# TSOC_USBUART2.net
KiCad netlist of a schematic drawn in EAGLE
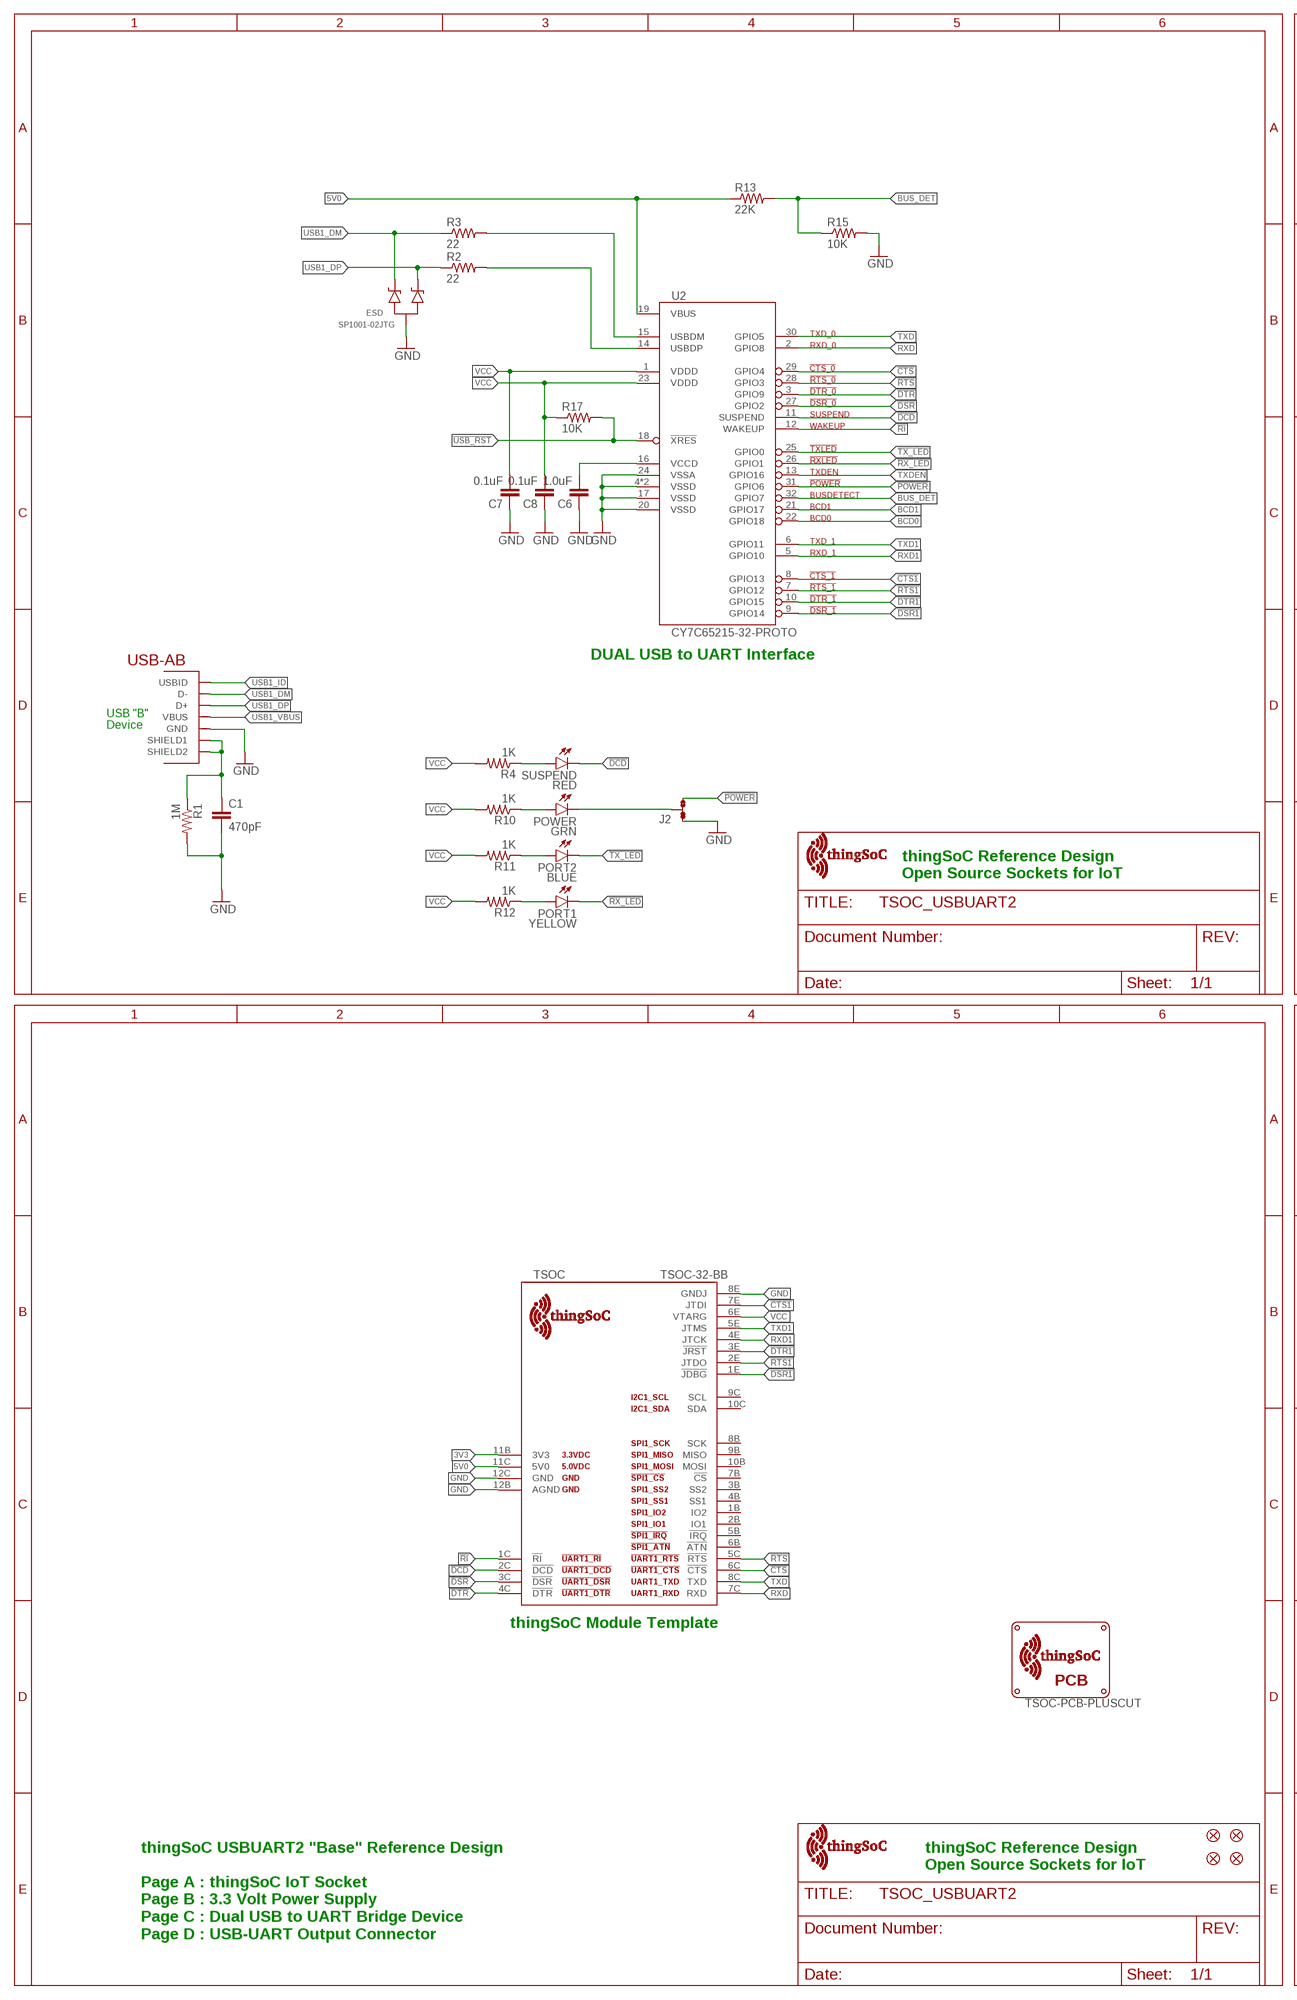
[diagram p0: schematic, sheet 1, part 1 of 2]
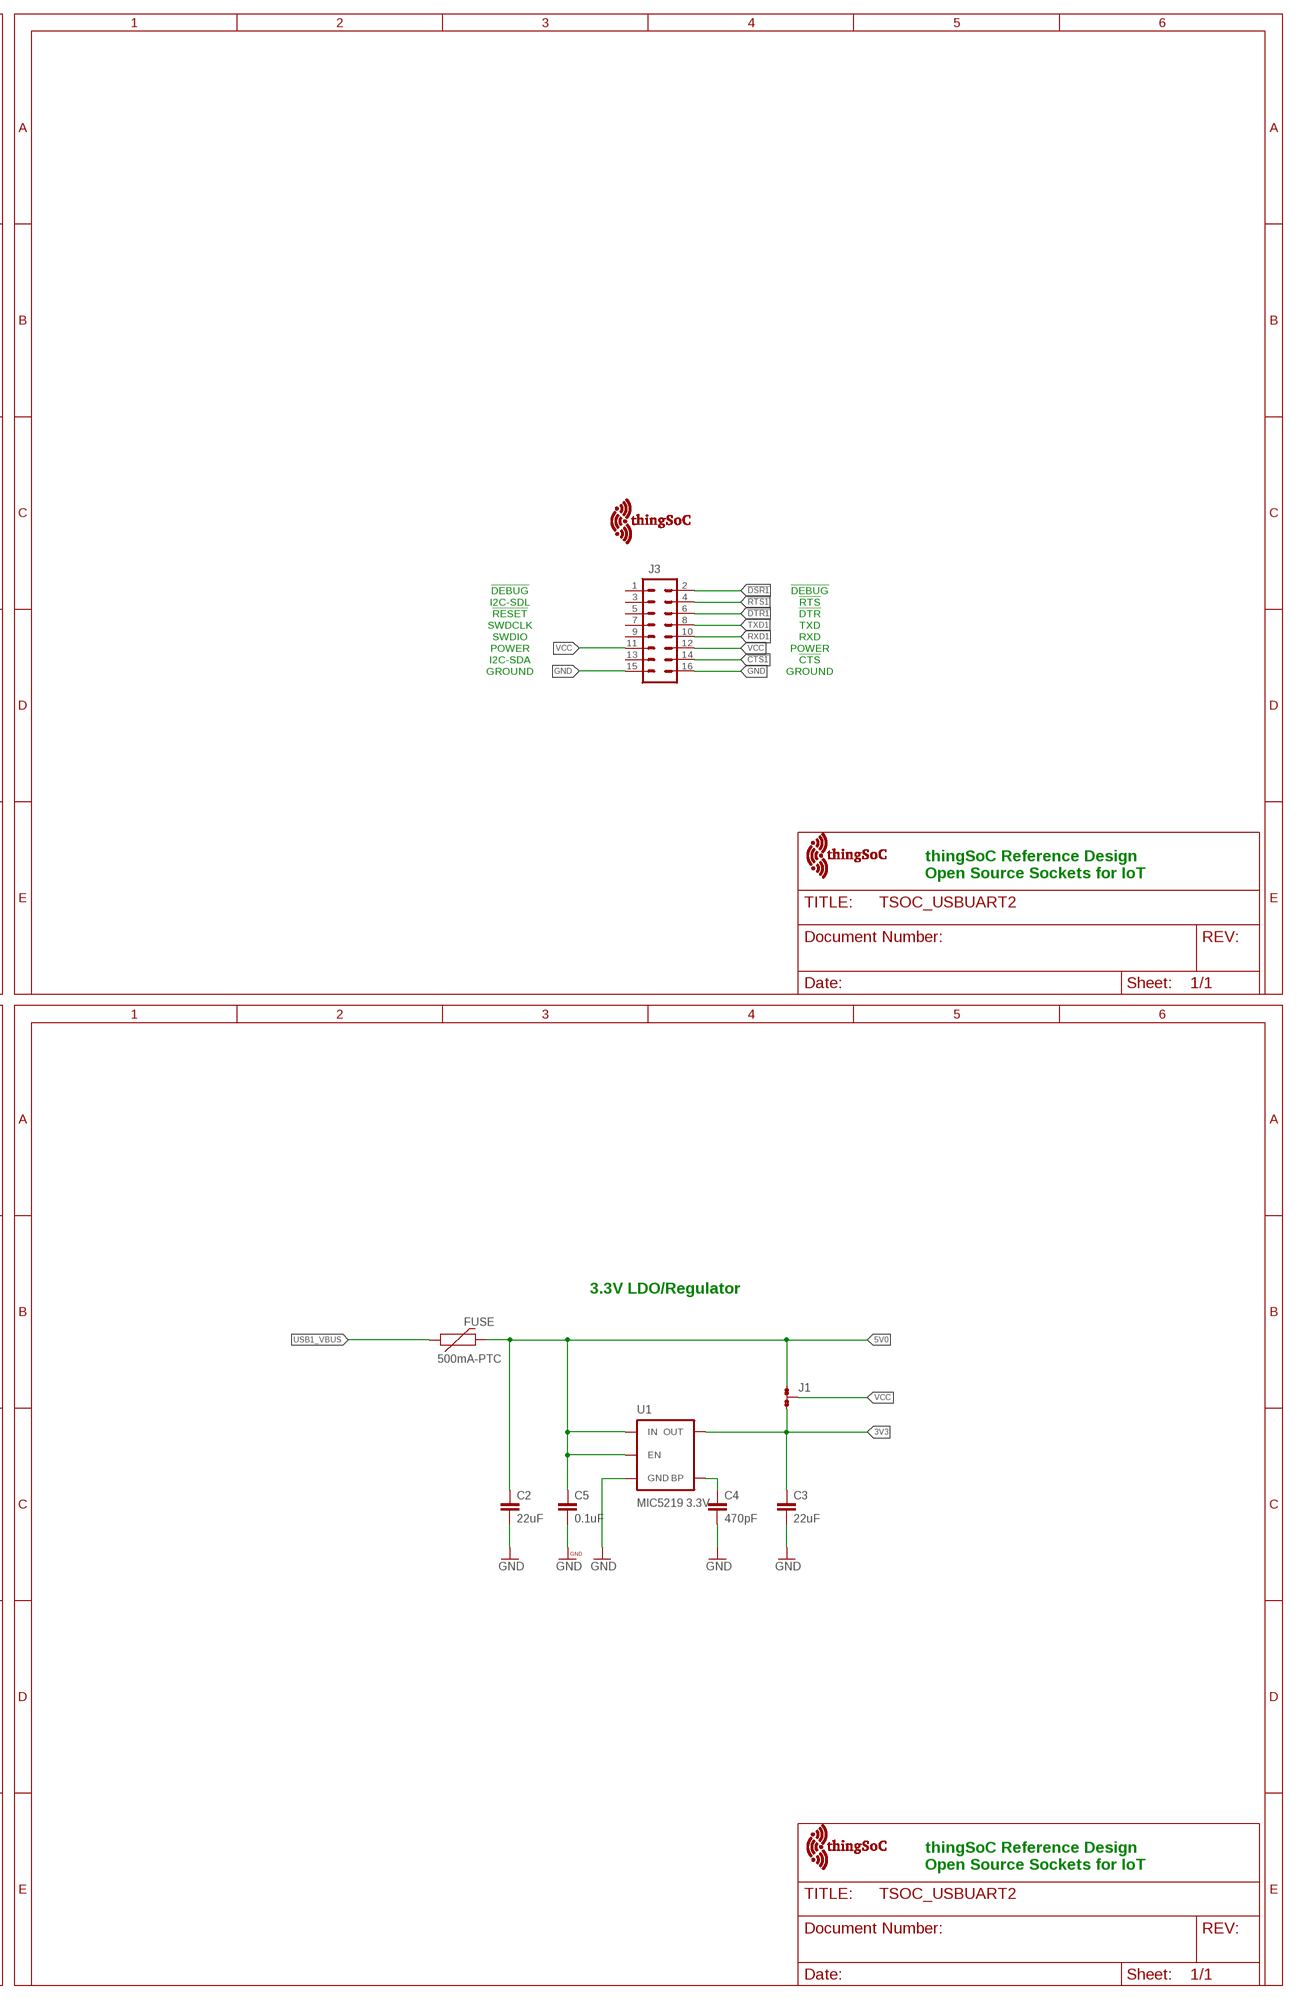
[diagram p1: schematic, sheet 1, part 2 of 2]

(export (version "E")
  (design (tool "Eeschema 10.0.6"))
  (components
    (comp (ref "C1")
      (value "470pF")
      (footprint "eagle-import:EIA-0603")
      (libsource (lib "eagle-import") (part "CAP-0603"))
    )
    (comp (ref "C2")
      (value "22uF")
      (footprint "eagle-import:EIA-1206")
      (libsource (lib "eagle-import") (part "CAP-1206"))
    )
    (comp (ref "C3")
      (value "22uF")
      (footprint "eagle-import:EIA-1206")
      (libsource (lib "eagle-import") (part "CAP-1206"))
    )
    (comp (ref "C4")
      (value "470pF")
      (footprint "eagle-import:EIA-0603")
      (libsource (lib "eagle-import") (part "CAP-0603"))
    )
    (comp (ref "C5")
      (value "0.1uF")
      (footprint "eagle-import:EIA-0603")
      (libsource (lib "eagle-import") (part "CAP-0603"))
    )
    (comp (ref "C6")
      (value "1.0uF")
      (footprint "eagle-import:EIA-0603")
      (libsource (lib "eagle-import") (part "CAP-0603"))
    )
    (comp (ref "C7")
      (value "0.1uF")
      (footprint "eagle-import:EIA-0603")
      (libsource (lib "eagle-import") (part "CAP-0603"))
    )
    (comp (ref "C8")
      (value "0.1uF")
      (footprint "eagle-import:EIA-0603")
      (libsource (lib "eagle-import") (part "CAP-0603"))
    )
    (comp (ref "ESD")
      (value "SP1001-02JTG")
      (footprint "eagle-import:SC70-3")
      (libsource (lib "eagle-import") (part "SP1001-02JTG"))
    )
    (comp (ref "FID1")
      (value "FIDUCIALUFIDUCIAL")
      (footprint "eagle-import:MICRO-FIDUCIAL")
      (libsource (lib "eagle-import") (part "FIDUCIALUFIDUCIAL"))
    )
    (comp (ref "FID2")
      (value "FIDUCIALUFIDUCIAL")
      (footprint "eagle-import:MICRO-FIDUCIAL")
      (libsource (lib "eagle-import") (part "FIDUCIALUFIDUCIAL"))
    )
    (comp (ref "FID3")
      (value "FIDUCIALUFIDUCIAL")
      (footprint "eagle-import:MICRO-FIDUCIAL")
      (libsource (lib "eagle-import") (part "FIDUCIALUFIDUCIAL"))
    )
    (comp (ref "FID4")
      (value "FIDUCIALUFIDUCIAL")
      (footprint "eagle-import:MICRO-FIDUCIAL")
      (libsource (lib "eagle-import") (part "FIDUCIALUFIDUCIAL"))
    )
    (comp (ref "FUSE")
      (value "500mA-PTC")
      (footprint "eagle-import:PTC-1206")
      (libsource (lib "eagle-import") (part "PTCSMD"))
    )
    (comp (ref "J1")
      (value "JMP-3-1_2")
      (footprint "eagle-import:JMP-3-1_2")
      (libsource (lib "eagle-import") (part "JMP-3-1_2"))
    )
    (comp (ref "J2")
      (value "JMP-3-1_2")
      (footprint "eagle-import:JMP-3-1_2")
      (libsource (lib "eagle-import") (part "JMP-3-1_2"))
    )
    (comp (ref "J3")
      (value "M08X2")
      (footprint "eagle-import:2X8")
      (libsource (lib "eagle-import") (part "M08X2"))
    )
    (comp (ref "PORT1")
      (value "YELLOW")
      (footprint "eagle-import:LED-0603")
      (libsource (lib "eagle-import") (part "LED0603"))
    )
    (comp (ref "PORT2")
      (value "BLUE")
      (footprint "eagle-import:LED-0603")
      (libsource (lib "eagle-import") (part "LED0603"))
    )
    (comp (ref "POWER")
      (value "GRN")
      (footprint "eagle-import:LED-0603")
      (libsource (lib "eagle-import") (part "LED0603"))
    )
    (comp (ref "R1")
      (value "1M")
      (footprint "eagle-import:EIA-0603")
      (libsource (lib "eagle-import") (part "RESISTOR-0603"))
    )
    (comp (ref "R2")
      (value "22")
      (footprint "eagle-import:EIA-0603")
      (libsource (lib "eagle-import") (part "RESISTOR-0603"))
    )
    (comp (ref "R3")
      (value "22")
      (footprint "eagle-import:EIA-0603")
      (libsource (lib "eagle-import") (part "RESISTOR-0603"))
    )
    (comp (ref "R4")
      (value "1K")
      (footprint "eagle-import:EIA-0603")
      (libsource (lib "eagle-import") (part "RESISTOR-0603"))
    )
    (comp (ref "R10")
      (value "1K")
      (footprint "eagle-import:EIA-0603")
      (libsource (lib "eagle-import") (part "RESISTOR-0603"))
    )
    (comp (ref "R11")
      (value "1K")
      (footprint "eagle-import:EIA-0603")
      (libsource (lib "eagle-import") (part "RESISTOR-0603"))
    )
    (comp (ref "R12")
      (value "1K")
      (footprint "eagle-import:EIA-0603")
      (libsource (lib "eagle-import") (part "RESISTOR-0603"))
    )
    (comp (ref "R13")
      (value "22K")
      (footprint "eagle-import:EIA-0603")
      (libsource (lib "eagle-import") (part "RESISTOR-0603"))
    )
    (comp (ref "R15")
      (value "10K")
      (footprint "eagle-import:EIA-0603")
      (libsource (lib "eagle-import") (part "RESISTOR-0603"))
    )
    (comp (ref "R17")
      (value "10K")
      (footprint "eagle-import:EIA-0603")
      (libsource (lib "eagle-import") (part "RESISTOR-0603"))
    )
    (comp (ref "SUSPEND")
      (value "RED")
      (footprint "eagle-import:LED-0603")
      (libsource (lib "eagle-import") (part "LED0603"))
    )
    (comp (ref "TSOC")
      (value "TSOC-32-BB")
      (footprint "eagle-import:TSOC-BB-S32")
      (libsource (lib "eagle-import") (part "TSOC-32-BB"))
    )
    (comp (ref "U$3")
      (value "TSOC-LOGO-LRG")
      (footprint "eagle-import:TSOC-LOGO-LRG")
      (libsource (lib "eagle-import") (part "TSOC-LOGO-LRG"))
    )
    (comp (ref "U$4")
      (value "TSOC-LOGO")
      (footprint "eagle-import:TSOC-LOGO-BLANK")
      (libsource (lib "eagle-import") (part "TSOC-LOGO"))
    )
    (comp (ref "U$5")
      (value "TSOC-LOGO")
      (footprint "eagle-import:TSOC-LOGO-BLANK")
      (libsource (lib "eagle-import") (part "TSOC-LOGO"))
    )
    (comp (ref "U$6")
      (value "TSOC-LOGO")
      (footprint "eagle-import:TSOC-LOGO-BLANK")
      (libsource (lib "eagle-import") (part "TSOC-LOGO"))
    )
    (comp (ref "U$7")
      (value "TSOC-PCB-PLUSCUT")
      (footprint "eagle-import:TSOC-BB-BRD-PLUS-CUT")
      (libsource (lib "eagle-import") (part "TSOC-PCB-PLUSCUT"))
    )
    (comp (ref "U$8")
      (value "TSOC-LOGO-SMALL")
      (footprint "eagle-import:TSOC-LOGO-SML")
      (libsource (lib "eagle-import") (part "TSOC-LOGO-SMALL"))
    )
    (comp (ref "U1")
      (value "MIC5219 3.3V")
      (footprint "eagle-import:SOT23-5")
      (libsource (lib "eagle-import") (part "V_REG_MIC52193.3V"))
    )
    (comp (ref "U2")
      (value "CY7C65215-32-PROTO")
      (footprint "eagle-import:QFN32-PROTO")
      (libsource (lib "eagle-import") (part "CY7C65215-32-PROTO"))
    )
    (comp (ref "USB")
      (value "USB_AB")
      (footprint "eagle-import:USB-AB-MICRO-SMD")
      (libsource (lib "eagle-import") (part "USB_AB"))
    )
  )
  (nets
    (net (code "1") (name "/~{CTS1}") (class "Default")
      (node (ref "J3") (pin "14") (pinfunction "14_14") (pintype "passive"))
      (node (ref "TSOC") (pin "7E") (pinfunction "JTDI_7E") (pintype "bidirectional"))
      (node (ref "U2") (pin "8") (pinfunction "GPIO13_8") (pintype "input"))
    )
    (net (code "2") (name "/~{CTS}") (class "Default")
      (node (ref "TSOC") (pin "6C") (pinfunction "~{CTS}_6C") (pintype "bidirectional"))
      (node (ref "U2") (pin "29") (pinfunction "GPIO4_29") (pintype "input"))
    )
    (net (code "3") (name "/~{DCD}") (class "Default")
      (node (ref "SUSPEND") (pin "C") (pinfunction "C_C") (pintype "passive"))
      (node (ref "TSOC") (pin "2C") (pinfunction "~{DCD}_2C") (pintype "bidirectional"))
      (node (ref "U2") (pin "11") (pinfunction "SUSPEND_11") (pintype "input"))
    )
    (net (code "4") (name "/~{DSR1}") (class "Default")
      (node (ref "J3") (pin "2") (pinfunction "2_2") (pintype "passive"))
      (node (ref "TSOC") (pin "1E") (pinfunction "~{JDBG}_1E") (pintype "bidirectional"))
      (node (ref "U2") (pin "9") (pinfunction "GPIO14_9") (pintype "input"))
    )
    (net (code "5") (name "/~{DSR}") (class "Default")
      (node (ref "TSOC") (pin "3C") (pinfunction "~{DSR}_3C") (pintype "bidirectional"))
      (node (ref "U2") (pin "27") (pinfunction "GPIO2_27") (pintype "input"))
    )
    (net (code "6") (name "/~{DTR1}") (class "Default")
      (node (ref "J3") (pin "6") (pinfunction "6_6") (pintype "passive"))
      (node (ref "TSOC") (pin "3E") (pinfunction "~{JRST}_3E") (pintype "bidirectional"))
      (node (ref "U2") (pin "10") (pinfunction "GPIO15_10") (pintype "output"))
    )
    (net (code "7") (name "/~{DTR}") (class "Default")
      (node (ref "TSOC") (pin "4C") (pinfunction "~{DTR}_4C") (pintype "bidirectional"))
      (node (ref "U2") (pin "3") (pinfunction "GPIO9_3") (pintype "output"))
    )
    (net (code "8") (name "/~{POWER}") (class "Default")
      (node (ref "J2") (pin "3") (pinfunction "3_3") (pintype "passive"))
      (node (ref "U2") (pin "31") (pinfunction "GPIO6_31") (pintype "input"))
    )
    (net (code "9") (name "/~{RI}") (class "Default")
      (node (ref "TSOC") (pin "1C") (pinfunction "~{RI}_1C") (pintype "bidirectional"))
      (node (ref "U2") (pin "12") (pinfunction "WAKEUP_12") (pintype "input"))
    )
    (net (code "10") (name "/~{RTS1}") (class "Default")
      (node (ref "J3") (pin "4") (pinfunction "4_4") (pintype "passive"))
      (node (ref "TSOC") (pin "2E") (pinfunction "JTDO_2E") (pintype "bidirectional"))
      (node (ref "U2") (pin "7") (pinfunction "GPIO12_7") (pintype "output"))
    )
    (net (code "11") (name "/~{RTS}") (class "Default")
      (node (ref "TSOC") (pin "5C") (pinfunction "~{RTS}_5C") (pintype "bidirectional"))
      (node (ref "U2") (pin "28") (pinfunction "GPIO3_28") (pintype "output"))
    )
    (net (code "12") (name "/~{RX_LED}") (class "Default")
      (node (ref "PORT1") (pin "C") (pinfunction "C_C") (pintype "passive"))
      (node (ref "U2") (pin "26") (pinfunction "GPIO1_26") (pintype "input"))
    )
    (net (code "13") (name "/~{TX_LED}") (class "Default")
      (node (ref "PORT2") (pin "C") (pinfunction "C_C") (pintype "passive"))
      (node (ref "U2") (pin "25") (pinfunction "GPIO0_25") (pintype "input"))
    )
    (net (code "14") (name "/~{USB_RST}") (class "Default")
      (node (ref "R17") (pin "2") (pinfunction "2_2") (pintype "passive"))
      (node (ref "U2") (pin "18") (pinfunction "~{XRES}_18") (pintype "input"))
    )
    (net (code "15") (name "3V3") (class "Default")
      (node (ref "C3") (pin "1") (pinfunction "1_1") (pintype "passive"))
      (node (ref "J1") (pin "3") (pinfunction "3_3") (pintype "passive"))
      (node (ref "TSOC") (pin "11B") (pinfunction "3V3_11B") (pintype "bidirectional"))
      (node (ref "U1") (pin "5") (pinfunction "OUT_5") (pintype "passive"))
    )
    (net (code "16") (name "5V0") (class "Default")
      (node (ref "C2") (pin "1") (pinfunction "1_1") (pintype "passive"))
      (node (ref "C5") (pin "1") (pinfunction "1_1") (pintype "passive"))
      (node (ref "FUSE") (pin "2") (pinfunction "2_2") (pintype "bidirectional"))
      (node (ref "J1") (pin "1") (pinfunction "1_1") (pintype "passive"))
      (node (ref "R13") (pin "1") (pinfunction "1_1") (pintype "passive"))
      (node (ref "TSOC") (pin "11C") (pinfunction "5V0_11C") (pintype "bidirectional"))
      (node (ref "U1") (pin "1") (pinfunction "IN_1") (pintype "input"))
      (node (ref "U1") (pin "3") (pinfunction "EN_3") (pintype "input"))
      (node (ref "U2") (pin "19") (pinfunction "VBUS_19") (pintype "power_in"))
    )
    (net (code "17") (name "BCD0") (class "Default")
      (node (ref "U2") (pin "22") (pinfunction "GPIO18_22") (pintype "input"))
    )
    (net (code "18") (name "BCD1") (class "Default")
      (node (ref "U2") (pin "21") (pinfunction "GPIO17_21") (pintype "input"))
    )
    (net (code "19") (name "BUS_DET") (class "Default")
      (node (ref "R13") (pin "2") (pinfunction "2_2") (pintype "passive"))
      (node (ref "R15") (pin "1") (pinfunction "1_1") (pintype "passive"))
      (node (ref "U2") (pin "32") (pinfunction "GPIO7_32") (pintype "input"))
    )
    (net (code "20") (name "GND") (class "Default")
      (node (ref "C1") (pin "2") (pinfunction "2_2") (pintype "passive"))
      (node (ref "C2") (pin "2") (pinfunction "2_2") (pintype "passive"))
      (node (ref "C3") (pin "2") (pinfunction "2_2") (pintype "passive"))
      (node (ref "C4") (pin "2") (pinfunction "2_2") (pintype "passive"))
      (node (ref "C5") (pin "2") (pinfunction "2_2") (pintype "passive"))
      (node (ref "C6") (pin "1") (pinfunction "1_1") (pintype "passive"))
      (node (ref "C7") (pin "1") (pinfunction "1_1") (pintype "passive"))
      (node (ref "C8") (pin "1") (pinfunction "1_1") (pintype "passive"))
      (node (ref "ESD") (pin "3") (pinfunction "A_3") (pintype "passive"))
      (node (ref "J2") (pin "1") (pinfunction "1_1") (pintype "passive"))
      (node (ref "J3") (pin "15") (pinfunction "15_15") (pintype "passive"))
      (node (ref "J3") (pin "16") (pinfunction "16_16") (pintype "passive"))
      (node (ref "R1") (pin "2") (pinfunction "2_2") (pintype "passive"))
      (node (ref "R15") (pin "2") (pinfunction "2_2") (pintype "passive"))
      (node (ref "TSOC") (pin "12B") (pinfunction "AGND_12B") (pintype "bidirectional"))
      (node (ref "TSOC") (pin "12C") (pinfunction "GND_12C") (pintype "bidirectional"))
      (node (ref "TSOC") (pin "8E") (pinfunction "GNDJ_8E") (pintype "bidirectional"))
      (node (ref "U1") (pin "2") (pinfunction "GND_2") (pintype "input"))
      (node (ref "U2") (pin "17") (pinfunction "VSSD_17") (pintype "power_in"))
      (node (ref "U2") (pin "20") (pinfunction "VSSD_20") (pintype "power_in"))
      (node (ref "U2") (pin "24") (pinfunction "VSSA_24") (pintype "power_in"))
      (node (ref "U2") (pin "4") (pinfunction "VSSD_4") (pintype "power_in"))
      (node (ref "U2") (pin "EXP") (pinfunction "VSSD_EXP") (pintype "power_in"))
      (node (ref "USB") (pin "GND") (pinfunction "GND_GND") (pintype "bidirectional"))
    )
    (net (code "21") (name "Net-(C1-Pad1)") (class "Default")
      (node (ref "C1") (pin "1") (pinfunction "1_1") (pintype "passive"))
      (node (ref "R1") (pin "1") (pinfunction "1_1") (pintype "passive"))
      (node (ref "USB") (pin "SHIELD1") (pinfunction "SHIELD1_SHIELD1") (pintype "bidirectional"))
      (node (ref "USB") (pin "SHIELD2") (pinfunction "SHIELD2_SHIELD2") (pintype "bidirectional"))
    )
    (net (code "22") (name "Net-(J2-Pad2)") (class "Default")
      (node (ref "J2") (pin "2") (pinfunction "2_2") (pintype "passive"))
      (node (ref "POWER") (pin "C") (pinfunction "C_C") (pintype "passive"))
    )
    (net (code "23") (name "Net-(PORT1-PadA)") (class "Default")
      (node (ref "PORT1") (pin "A") (pinfunction "A_A") (pintype "passive"))
      (node (ref "R12") (pin "1") (pinfunction "1_1") (pintype "passive"))
    )
    (net (code "24") (name "Net-(PORT2-PadA)") (class "Default")
      (node (ref "PORT2") (pin "A") (pinfunction "A_A") (pintype "passive"))
      (node (ref "R11") (pin "1") (pinfunction "1_1") (pintype "passive"))
    )
    (net (code "25") (name "Net-(POWER-PadA)") (class "Default")
      (node (ref "POWER") (pin "A") (pinfunction "A_A") (pintype "passive"))
      (node (ref "R10") (pin "1") (pinfunction "1_1") (pintype "passive"))
    )
    (net (code "26") (name "Net-(R4-Pad1)") (class "Default")
      (node (ref "R4") (pin "1") (pinfunction "1_1") (pintype "passive"))
      (node (ref "SUSPEND") (pin "A") (pinfunction "A_A") (pintype "passive"))
    )
    (net (code "27") (name "Net-(U1-BP)") (class "Default")
      (node (ref "C4") (pin "1") (pinfunction "1_1") (pintype "passive"))
      (node (ref "U1") (pin "4") (pinfunction "BP_4") (pintype "input"))
    )
    (net (code "28") (name "Net-(U2-USBDM)") (class "Default")
      (node (ref "R3") (pin "2") (pinfunction "2_2") (pintype "passive"))
      (node (ref "U2") (pin "15") (pinfunction "USBDM_15") (pintype "bidirectional"))
    )
    (net (code "29") (name "Net-(U2-USBDP)") (class "Default")
      (node (ref "R2") (pin "2") (pinfunction "2_2") (pintype "passive"))
      (node (ref "U2") (pin "14") (pinfunction "USBDP_14") (pintype "bidirectional"))
    )
    (net (code "30") (name "Net-(U2-VCCD)") (class "Default")
      (node (ref "C6") (pin "2") (pinfunction "2_2") (pintype "passive"))
      (node (ref "U2") (pin "16") (pinfunction "VCCD_16") (pintype "output"))
    )
    (net (code "31") (name "RXD") (class "Default")
      (node (ref "TSOC") (pin "7C") (pinfunction "RXD_7C") (pintype "bidirectional"))
      (node (ref "U2") (pin "2") (pinfunction "GPIO8_2") (pintype "input"))
    )
    (net (code "32") (name "RXD1") (class "Default")
      (node (ref "J3") (pin "10") (pinfunction "10_10") (pintype "passive"))
      (node (ref "TSOC") (pin "4E") (pinfunction "JTCK_4E") (pintype "bidirectional"))
      (node (ref "U2") (pin "5") (pinfunction "GPIO10_5") (pintype "input"))
    )
    (net (code "33") (name "TXD") (class "Default")
      (node (ref "TSOC") (pin "8C") (pinfunction "TXD_8C") (pintype "bidirectional"))
      (node (ref "U2") (pin "30") (pinfunction "GPIO5_30") (pintype "output"))
    )
    (net (code "34") (name "TXD1") (class "Default")
      (node (ref "J3") (pin "8") (pinfunction "8_8") (pintype "passive"))
      (node (ref "TSOC") (pin "5E") (pinfunction "JTMS_5E") (pintype "bidirectional"))
      (node (ref "U2") (pin "6") (pinfunction "GPIO11_6") (pintype "output"))
    )
    (net (code "35") (name "TXDEN") (class "Default")
      (node (ref "U2") (pin "13") (pinfunction "GPIO16_13") (pintype "output"))
    )
    (net (code "36") (name "USB1_DM") (class "Default")
      (node (ref "ESD") (pin "2") (pinfunction "C2_2") (pintype "passive"))
      (node (ref "R3") (pin "1") (pinfunction "1_1") (pintype "passive"))
      (node (ref "USB") (pin "D-") (pinfunction "D-_D-") (pintype "bidirectional"))
    )
    (net (code "37") (name "USB1_DP") (class "Default")
      (node (ref "ESD") (pin "1") (pinfunction "C1_1") (pintype "passive"))
      (node (ref "R2") (pin "1") (pinfunction "1_1") (pintype "passive"))
      (node (ref "USB") (pin "D+") (pinfunction "D+_D+") (pintype "bidirectional"))
    )
    (net (code "38") (name "USB1_ID") (class "Default")
      (node (ref "USB") (pin "ID") (pinfunction "USBID_ID") (pintype "bidirectional"))
    )
    (net (code "39") (name "USB1_VBUS") (class "Default")
      (node (ref "FUSE") (pin "1") (pinfunction "1_1") (pintype "bidirectional"))
      (node (ref "USB") (pin "VBUS") (pinfunction "VBUS_VBUS") (pintype "bidirectional"))
    )
    (net (code "40") (name "VCC") (class "Default")
      (node (ref "C7") (pin "2") (pinfunction "2_2") (pintype "passive"))
      (node (ref "C8") (pin "2") (pinfunction "2_2") (pintype "passive"))
      (node (ref "J1") (pin "2") (pinfunction "2_2") (pintype "passive"))
      (node (ref "J3") (pin "11") (pinfunction "11_11") (pintype "passive"))
      (node (ref "J3") (pin "12") (pinfunction "12_12") (pintype "passive"))
      (node (ref "R10") (pin "2") (pinfunction "2_2") (pintype "passive"))
      (node (ref "R11") (pin "2") (pinfunction "2_2") (pintype "passive"))
      (node (ref "R12") (pin "2") (pinfunction "2_2") (pintype "passive"))
      (node (ref "R17") (pin "1") (pinfunction "1_1") (pintype "passive"))
      (node (ref "R4") (pin "2") (pinfunction "2_2") (pintype "passive"))
      (node (ref "TSOC") (pin "6E") (pinfunction "VTARG_6E") (pintype "bidirectional"))
      (node (ref "U2") (pin "1") (pinfunction "VDDD_1") (pintype "power_in"))
      (node (ref "U2") (pin "23") (pinfunction "VDDD_23") (pintype "power_in"))
    )
    (net (code "41") (name "unconnected-(J3-Pad1)") (class "Default")
      (node (ref "J3") (pin "1") (pinfunction "1_1") (pintype "passive"))
    )
    (net (code "42") (name "unconnected-(J3-Pad3)") (class "Default")
      (node (ref "J3") (pin "3") (pinfunction "3_3") (pintype "passive"))
    )
    (net (code "43") (name "unconnected-(J3-Pad5)") (class "Default")
      (node (ref "J3") (pin "5") (pinfunction "5_5") (pintype "passive"))
    )
    (net (code "44") (name "unconnected-(J3-Pad7)") (class "Default")
      (node (ref "J3") (pin "7") (pinfunction "7_7") (pintype "passive"))
    )
    (net (code "45") (name "unconnected-(J3-Pad9)") (class "Default")
      (node (ref "J3") (pin "9") (pinfunction "9_9") (pintype "passive"))
    )
    (net (code "46") (name "unconnected-(J3-Pad13)") (class "Default")
      (node (ref "J3") (pin "13") (pinfunction "13_13") (pintype "passive"))
    )
    (net (code "47") (name "unconnected-(TSOC-IO1-Pad2B)") (class "Default")
      (node (ref "TSOC") (pin "2B") (pinfunction "IO1_2B") (pintype "bidirectional"))
    )
    (net (code "48") (name "unconnected-(TSOC-IO2-Pad1B)") (class "Default")
      (node (ref "TSOC") (pin "1B") (pinfunction "IO2_1B") (pintype "bidirectional"))
    )
    (net (code "49") (name "unconnected-(TSOC-MISO-Pad9B)") (class "Default")
      (node (ref "TSOC") (pin "9B") (pinfunction "MISO_9B") (pintype "bidirectional"))
    )
    (net (code "50") (name "unconnected-(TSOC-MOSI-Pad10B)") (class "Default")
      (node (ref "TSOC") (pin "10B") (pinfunction "MOSI_10B") (pintype "bidirectional"))
    )
    (net (code "51") (name "unconnected-(TSOC-SCK-Pad8B)") (class "Default")
      (node (ref "TSOC") (pin "8B") (pinfunction "SCK_8B") (pintype "bidirectional"))
    )
    (net (code "52") (name "unconnected-(TSOC-SCL-Pad9C)") (class "Default")
      (node (ref "TSOC") (pin "9C") (pinfunction "SCL_9C") (pintype "bidirectional"))
    )
    (net (code "53") (name "unconnected-(TSOC-SDA-Pad10C)") (class "Default")
      (node (ref "TSOC") (pin "10C") (pinfunction "SDA_10C") (pintype "bidirectional"))
    )
    (net (code "54") (name "unconnected-(TSOC-SS1-Pad4B)") (class "Default")
      (node (ref "TSOC") (pin "4B") (pinfunction "SS1_4B") (pintype "bidirectional"))
    )
    (net (code "55") (name "unconnected-(TSOC-SS2-Pad3B)") (class "Default")
      (node (ref "TSOC") (pin "3B") (pinfunction "SS2_3B") (pintype "bidirectional"))
    )
    (net (code "56") (name "unconnected-(TSOC-~{ATN}-Pad6B)") (class "Default")
      (node (ref "TSOC") (pin "6B") (pinfunction "~{ATN}_6B") (pintype "bidirectional"))
    )
    (net (code "57") (name "unconnected-(TSOC-~{CS}-Pad7B)") (class "Default")
      (node (ref "TSOC") (pin "7B") (pinfunction "~{CS}_7B") (pintype "bidirectional"))
    )
    (net (code "58") (name "unconnected-(TSOC-~{IRQ}-Pad5B)") (class "Default")
      (node (ref "TSOC") (pin "5B") (pinfunction "~{IRQ}_5B") (pintype "bidirectional"))
    )
  )
)
